# sensor.net
KiCad netlist of a schematic drawn in Altium Designer
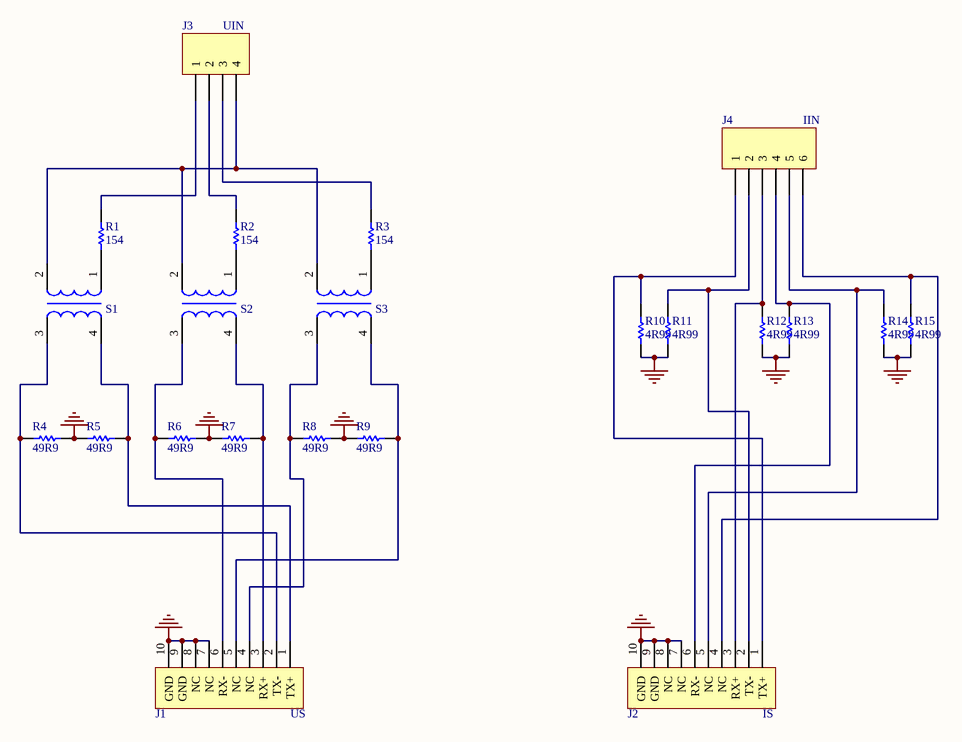
[diagram p0: sensor.SchDoc]

(export (version "E")
  (design (tool "Eeschema 10.0.6"))
  (components
    (comp (ref "J1")
      (value "US")
      (footprint "RJ-45")
      (description "RJ45水晶座")
      (libsource (lib "UC-SCH") (part "RJ45"))
    )
    (comp (ref "J2")
      (value "IS")
      (footprint "RJ-45")
      (description "RJ45水晶座")
      (libsource (lib "UC-SCH") (part "RJ45"))
    )
    (comp (ref "J3")
      (value "UIN")
      (footprint "2EDG-3.81-4P")
      (description "Header, 4-Pin")
      (fields (field (name "PUBLISHER") "Altium Limited"))
      (libsource (lib "Miscellaneous Connectors") (part "MHDR1X4"))
    )
    (comp (ref "J4")
      (value "IIN")
      (footprint "2EDG-3.81-6P")
      (description "Header, 6-Pin")
      (fields (field (name "PUBLISHER") "Altium Limited"))
      (libsource (lib "Miscellaneous Connectors") (part "MHDR1X6"))
    )
    (comp (ref "R1")
      (value "154")
      (footprint "R1W")
      (description "电阻")
      (fields (field (name "PUBLISHER") "Altium Limited"))
      (libsource (lib "UC-SCH") (part "Res"))
    )
    (comp (ref "R2")
      (value "154")
      (footprint "R1W")
      (description "电阻")
      (fields (field (name "PUBLISHER") "Altium Limited"))
      (libsource (lib "UC-SCH") (part "Res"))
    )
    (comp (ref "R3")
      (value "154")
      (footprint "R1W")
      (description "电阻")
      (fields (field (name "PUBLISHER") "Altium Limited"))
      (libsource (lib "UC-SCH") (part "Res"))
    )
    (comp (ref "R4")
      (value "49R9")
      (footprint "0805")
      (description "Resistor")
      (fields (field (name "PUBLISHER") "Altium Limited"))
      (libsource (lib "WeijaySch") (part "Res"))
    )
    (comp (ref "R5")
      (value "49R9")
      (footprint "0805")
      (description "Resistor")
      (fields (field (name "PUBLISHER") "Altium Limited"))
      (libsource (lib "WeijaySch") (part "Res"))
    )
    (comp (ref "R6")
      (value "49R9")
      (footprint "0805")
      (description "Resistor")
      (fields (field (name "PUBLISHER") "Altium Limited"))
      (libsource (lib "WeijaySch") (part "Res"))
    )
    (comp (ref "R7")
      (value "49R9")
      (footprint "0805")
      (description "Resistor")
      (fields (field (name "PUBLISHER") "Altium Limited"))
      (libsource (lib "WeijaySch") (part "Res"))
    )
    (comp (ref "R8")
      (value "49R9")
      (footprint "0805")
      (description "Resistor")
      (fields (field (name "PUBLISHER") "Altium Limited"))
      (libsource (lib "WeijaySch") (part "Res"))
    )
    (comp (ref "R9")
      (value "49R9")
      (footprint "0805")
      (description "Resistor")
      (fields (field (name "PUBLISHER") "Altium Limited"))
      (libsource (lib "WeijaySch") (part "Res"))
    )
    (comp (ref "R10")
      (value "4R99")
      (footprint "0805")
      (description "Resistor")
      (fields (field (name "PUBLISHER") "Altium Limited"))
      (libsource (lib "WeijaySch") (part "Res"))
    )
    (comp (ref "R11")
      (value "4R99")
      (footprint "0805")
      (description "Resistor")
      (fields (field (name "PUBLISHER") "Altium Limited"))
      (libsource (lib "WeijaySch") (part "Res"))
    )
    (comp (ref "R12")
      (value "4R99")
      (footprint "0805")
      (description "Resistor")
      (fields (field (name "PUBLISHER") "Altium Limited"))
      (libsource (lib "WeijaySch") (part "Res"))
    )
    (comp (ref "R13")
      (value "4R99")
      (footprint "0805")
      (description "Resistor")
      (fields (field (name "PUBLISHER") "Altium Limited"))
      (libsource (lib "WeijaySch") (part "Res"))
    )
    (comp (ref "R14")
      (value "4R99")
      (footprint "0805")
      (description "Resistor")
      (fields (field (name "PUBLISHER") "Altium Limited"))
      (libsource (lib "WeijaySch") (part "Res"))
    )
    (comp (ref "R15")
      (value "4R99")
      (footprint "0805")
      (description "Resistor")
      (fields (field (name "PUBLISHER") "Altium Limited"))
      (libsource (lib "WeijaySch") (part "Res"))
    )
    (comp (ref "S1")
      (value "US")
      (footprint "US")
      (description "电压互感器")
      (libsource (lib "UC-SCH") (part "US"))
    )
    (comp (ref "S2")
      (value "US")
      (footprint "US")
      (description "电压互感器")
      (libsource (lib "UC-SCH") (part "US"))
    )
    (comp (ref "S3")
      (value "US")
      (footprint "US")
      (description "电压互感器")
      (libsource (lib "UC-SCH") (part "US"))
    )
  )
  (nets
    (net (code "1") (name "GND") (class "Default")
      (node (ref "J1") (pin "10") (pinfunction "GND_10") (pintype "passive"))
      (node (ref "J1") (pin "7") (pinfunction "NC_7") (pintype "passive"))
      (node (ref "J1") (pin "8") (pinfunction "NC_8") (pintype "passive"))
      (node (ref "J1") (pin "9") (pinfunction "GND_9") (pintype "passive"))
      (node (ref "J2") (pin "10") (pinfunction "GND_10") (pintype "passive"))
      (node (ref "J2") (pin "7") (pinfunction "NC_7") (pintype "passive"))
      (node (ref "J2") (pin "8") (pinfunction "NC_8") (pintype "passive"))
      (node (ref "J2") (pin "9") (pinfunction "GND_9") (pintype "passive"))
      (node (ref "R10") (pin "1") (pinfunction "1_1") (pintype "passive"))
      (node (ref "R11") (pin "1") (pinfunction "1_1") (pintype "passive"))
      (node (ref "R12") (pin "1") (pinfunction "1_1") (pintype "passive"))
      (node (ref "R13") (pin "1") (pinfunction "1_1") (pintype "passive"))
      (node (ref "R14") (pin "1") (pinfunction "1_1") (pintype "passive"))
      (node (ref "R15") (pin "1") (pinfunction "1_1") (pintype "passive"))
      (node (ref "R4") (pin "1") (pinfunction "1_1") (pintype "passive"))
      (node (ref "R5") (pin "2") (pinfunction "2_2") (pintype "passive"))
      (node (ref "R6") (pin "1") (pinfunction "1_1") (pintype "passive"))
      (node (ref "R7") (pin "2") (pinfunction "2_2") (pintype "passive"))
      (node (ref "R8") (pin "1") (pinfunction "1_1") (pintype "passive"))
      (node (ref "R9") (pin "2") (pinfunction "2_2") (pintype "passive"))
    )
    (net (code "2") (name "Net-(J1-NC-Pad4)") (class "Default")
      (node (ref "J1") (pin "4") (pinfunction "NC_4") (pintype "passive"))
      (node (ref "R8") (pin "2") (pinfunction "2_2") (pintype "passive"))
      (node (ref "S3") (pin "3") (pinfunction "3_3") (pintype "passive"))
    )
    (net (code "3") (name "Net-(J1-NC-Pad5)") (class "Default")
      (node (ref "J1") (pin "5") (pinfunction "NC_5") (pintype "passive"))
      (node (ref "R9") (pin "1") (pinfunction "1_1") (pintype "passive"))
      (node (ref "S3") (pin "4") (pinfunction "4_4") (pintype "passive"))
    )
    (net (code "4") (name "Net-(J1-RX+)") (class "Default")
      (node (ref "J1") (pin "3") (pinfunction "RX+_3") (pintype "passive"))
      (node (ref "R7") (pin "1") (pinfunction "1_1") (pintype "passive"))
      (node (ref "S2") (pin "4") (pinfunction "4_4") (pintype "passive"))
    )
    (net (code "5") (name "Net-(J1-RX-)") (class "Default")
      (node (ref "J1") (pin "6") (pinfunction "RX-_6") (pintype "passive"))
      (node (ref "R6") (pin "2") (pinfunction "2_2") (pintype "passive"))
      (node (ref "S2") (pin "3") (pinfunction "3_3") (pintype "passive"))
    )
    (net (code "6") (name "Net-(J1-TX+)") (class "Default")
      (node (ref "J1") (pin "1") (pinfunction "TX+_1") (pintype "passive"))
      (node (ref "R5") (pin "1") (pinfunction "1_1") (pintype "passive"))
      (node (ref "S1") (pin "4") (pinfunction "4_4") (pintype "passive"))
    )
    (net (code "7") (name "Net-(J1-TX-)") (class "Default")
      (node (ref "J1") (pin "2") (pinfunction "TX-_2") (pintype "passive"))
      (node (ref "R4") (pin "2") (pinfunction "2_2") (pintype "passive"))
      (node (ref "S1") (pin "3") (pinfunction "3_3") (pintype "passive"))
    )
    (net (code "8") (name "Net-(J2-NC-Pad4)") (class "Default")
      (node (ref "J2") (pin "4") (pinfunction "NC_4") (pintype "passive"))
      (node (ref "J4") (pin "6") (pinfunction "6_6") (pintype "passive"))
      (node (ref "R15") (pin "2") (pinfunction "2_2") (pintype "passive"))
    )
    (net (code "9") (name "Net-(J2-NC-Pad5)") (class "Default")
      (node (ref "J2") (pin "5") (pinfunction "NC_5") (pintype "passive"))
      (node (ref "J4") (pin "5") (pinfunction "5_5") (pintype "passive"))
      (node (ref "R14") (pin "2") (pinfunction "2_2") (pintype "passive"))
    )
    (net (code "10") (name "Net-(J2-RX+)") (class "Default")
      (node (ref "J2") (pin "3") (pinfunction "RX+_3") (pintype "passive"))
      (node (ref "J4") (pin "3") (pinfunction "3_3") (pintype "passive"))
      (node (ref "R12") (pin "2") (pinfunction "2_2") (pintype "passive"))
    )
    (net (code "11") (name "Net-(J2-RX-)") (class "Default")
      (node (ref "J2") (pin "6") (pinfunction "RX-_6") (pintype "passive"))
      (node (ref "J4") (pin "4") (pinfunction "4_4") (pintype "passive"))
      (node (ref "R13") (pin "2") (pinfunction "2_2") (pintype "passive"))
    )
    (net (code "12") (name "Net-(J2-TX+)") (class "Default")
      (node (ref "J2") (pin "1") (pinfunction "TX+_1") (pintype "passive"))
      (node (ref "J4") (pin "1") (pinfunction "1_1") (pintype "passive"))
      (node (ref "R10") (pin "2") (pinfunction "2_2") (pintype "passive"))
    )
    (net (code "13") (name "Net-(J2-TX-)") (class "Default")
      (node (ref "J2") (pin "2") (pinfunction "TX-_2") (pintype "passive"))
      (node (ref "J4") (pin "2") (pinfunction "2_2") (pintype "passive"))
      (node (ref "R11") (pin "2") (pinfunction "2_2") (pintype "passive"))
    )
    (net (code "14") (name "Net-(J3-Pad1)") (class "Default")
      (node (ref "J3") (pin "1") (pinfunction "1_1") (pintype "passive"))
      (node (ref "R1") (pin "2") (pinfunction "2_2") (pintype "passive"))
    )
    (net (code "15") (name "Net-(J3-Pad2)") (class "Default")
      (node (ref "J3") (pin "2") (pinfunction "2_2") (pintype "passive"))
      (node (ref "R2") (pin "2") (pinfunction "2_2") (pintype "passive"))
    )
    (net (code "16") (name "Net-(J3-Pad3)") (class "Default")
      (node (ref "J3") (pin "3") (pinfunction "3_3") (pintype "passive"))
      (node (ref "R3") (pin "2") (pinfunction "2_2") (pintype "passive"))
    )
    (net (code "17") (name "Net-(J3-Pad4)") (class "Default")
      (node (ref "J3") (pin "4") (pinfunction "4_4") (pintype "passive"))
      (node (ref "S1") (pin "2") (pinfunction "2_2") (pintype "passive"))
      (node (ref "S2") (pin "2") (pinfunction "2_2") (pintype "passive"))
      (node (ref "S3") (pin "2") (pinfunction "2_2") (pintype "passive"))
    )
    (net (code "18") (name "Net-(R1-Pad1)") (class "Default")
      (node (ref "R1") (pin "1") (pinfunction "1_1") (pintype "passive"))
      (node (ref "S1") (pin "1") (pinfunction "1_1") (pintype "passive"))
    )
    (net (code "19") (name "Net-(R2-Pad1)") (class "Default")
      (node (ref "R2") (pin "1") (pinfunction "1_1") (pintype "passive"))
      (node (ref "S2") (pin "1") (pinfunction "1_1") (pintype "passive"))
    )
    (net (code "20") (name "Net-(R3-Pad1)") (class "Default")
      (node (ref "R3") (pin "1") (pinfunction "1_1") (pintype "passive"))
      (node (ref "S3") (pin "1") (pinfunction "1_1") (pintype "passive"))
    )
  )
)
